# ABS-Pro-Mini.net
KiCad netlist of a schematic drawn in EAGLE
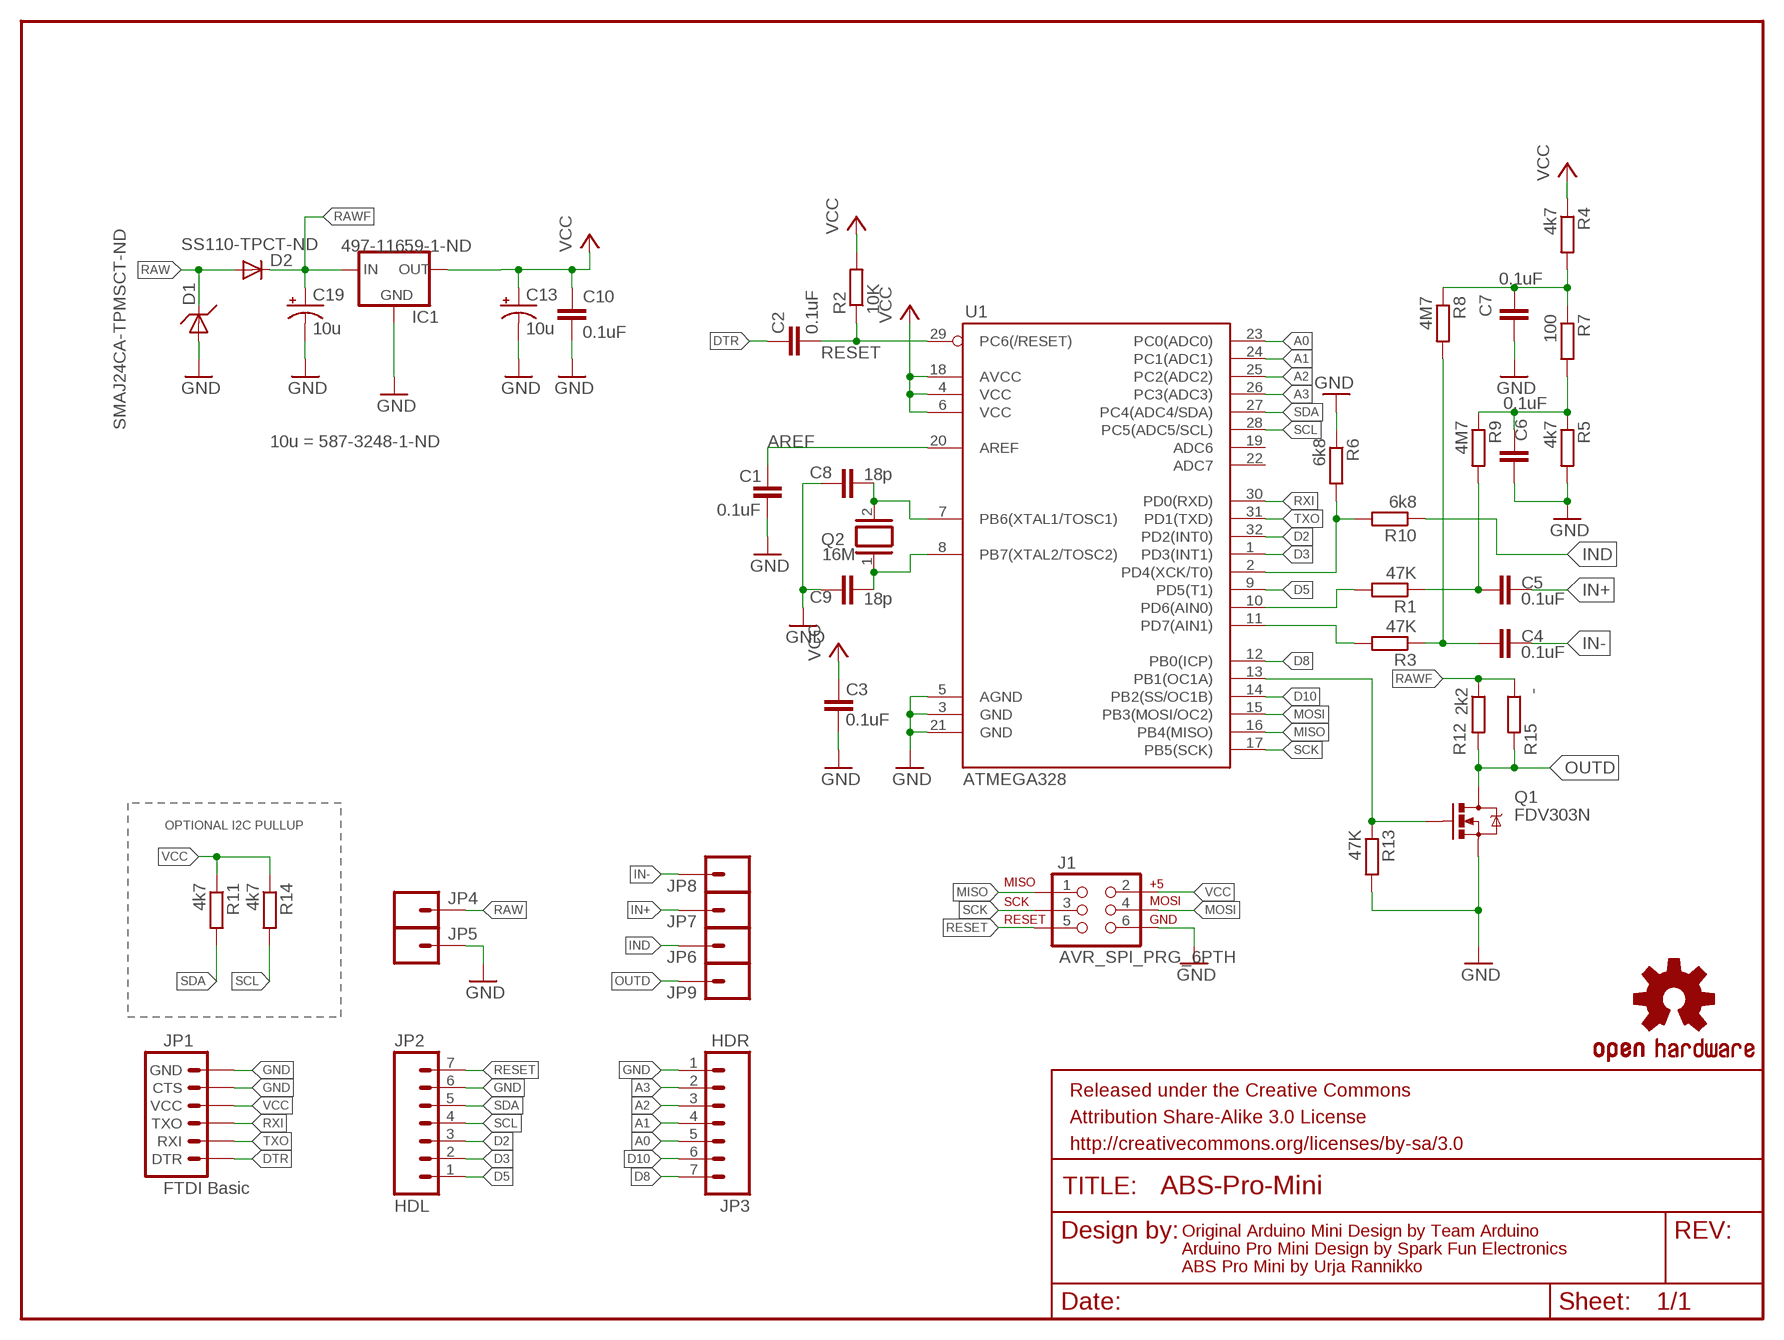
[diagram p0: schematic, sheet 1]

(export (version "E")
  (design (tool "Eeschema 10.0.6"))
  (components
    (comp (ref "C1")
      (value "0.1uF")
      (footprint "eagle-import:0603-CAP")
      (libsource (lib "eagle-import") (part "CAP0603-CAP"))
    )
    (comp (ref "C2")
      (value "0.1uF")
      (footprint "eagle-import:0603-CAP")
      (libsource (lib "eagle-import") (part "CAP0603-CAP"))
    )
    (comp (ref "C3")
      (value "0.1uF")
      (footprint "eagle-import:0603-CAP")
      (libsource (lib "eagle-import") (part "CAP0603-CAP"))
    )
    (comp (ref "C4")
      (value "0.1uF")
      (footprint "eagle-import:0603-CAP")
      (libsource (lib "eagle-import") (part "CAP0603-CAP"))
    )
    (comp (ref "C5")
      (value "0.1uF")
      (footprint "eagle-import:0603-CAP")
      (libsource (lib "eagle-import") (part "CAP0603-CAP"))
    )
    (comp (ref "C6")
      (value "0.1uF")
      (footprint "eagle-import:0603-CAP")
      (libsource (lib "eagle-import") (part "CAP0603-CAP"))
    )
    (comp (ref "C7")
      (value "0.1uF")
      (footprint "eagle-import:0603-CAP")
      (libsource (lib "eagle-import") (part "CAP0603-CAP"))
    )
    (comp (ref "C8")
      (value "18p")
      (footprint "eagle-import:0603-CAP")
      (libsource (lib "eagle-import") (part "CAP0603-CAP"))
    )
    (comp (ref "C9")
      (value "18p")
      (footprint "eagle-import:0603-CAP")
      (libsource (lib "eagle-import") (part "CAP0603-CAP"))
    )
    (comp (ref "C10")
      (value "0.1uF")
      (footprint "eagle-import:0603-CAP")
      (libsource (lib "eagle-import") (part "CAP0603-CAP"))
    )
    (comp (ref "C13")
      (value "10u")
      (footprint "eagle-import:EIA3216")
      (libsource (lib "eagle-import") (part "CAP_POL1206"))
    )
    (comp (ref "C19")
      (value "10u")
      (footprint "eagle-import:EIA3216")
      (libsource (lib "eagle-import") (part "CAP_POL1206"))
    )
    (comp (ref "D1")
      (value "SMAJ24CA-TPMSCT-ND")
      (footprint "eagle-import:SMA-DIODE")
      (libsource (lib "eagle-import") (part "DIODESMA"))
    )
    (comp (ref "D2")
      (value "SS110-TPCT-ND")
      (footprint "eagle-import:SMA-DIODE")
      (libsource (lib "eagle-import") (part "DIODESMA"))
    )
    (comp (ref "FRAME1")
      (value "FRAME-LETTER")
      (footprint "eagle-import:CREATIVE_COMMONS")
      (libsource (lib "eagle-import") (part "FRAME-LETTER"))
    )
    (comp (ref "IC1")
      (value "497-11659-1-ND")
      (footprint "eagle-import:SOT223")
      (libsource (lib "eagle-import") (part "V_REG_MIC2920MG"))
    )
    (comp (ref "J1")
      (value "AVR_SPI_PRG_6PTH")
      (footprint "eagle-import:2X3")
      (libsource (lib "eagle-import") (part "AVR_SPI_PRG_6PTH"))
    )
    (comp (ref "JP1")
      (value "FTDI Basic")
      (footprint "eagle-import:1X06")
      (libsource (lib "eagle-import") (part "ARDUINO_SERIAL_PROGRAMPTH"))
    )
    (comp (ref "JP2")
      (value "HDL")
      (footprint "eagle-import:1X07")
      (libsource (lib "eagle-import") (part "M07"))
    )
    (comp (ref "JP3")
      (value "HDR")
      (footprint "eagle-import:1X07")
      (libsource (lib "eagle-import") (part "M07"))
    )
    (comp (ref "JP4")
      (value "M01PTH_2MM")
      (footprint "eagle-import:1X01_2MM")
      (libsource (lib "eagle-import") (part "M01PTH_2MM"))
    )
    (comp (ref "JP5")
      (value "M01PTH_2MM")
      (footprint "eagle-import:1X01_2MM")
      (libsource (lib "eagle-import") (part "M01PTH_2MM"))
    )
    (comp (ref "JP6")
      (value "M01PTH_2MM")
      (footprint "eagle-import:1X01_2MM")
      (libsource (lib "eagle-import") (part "M01PTH_2MM"))
    )
    (comp (ref "JP7")
      (value "M01PTH_2MM")
      (footprint "eagle-import:1X01_2MM")
      (libsource (lib "eagle-import") (part "M01PTH_2MM"))
    )
    (comp (ref "JP8")
      (value "M01PTH_2MM")
      (footprint "eagle-import:1X01_2MM")
      (libsource (lib "eagle-import") (part "M01PTH_2MM"))
    )
    (comp (ref "JP9")
      (value "M01PTH_2MM")
      (footprint "eagle-import:1X01_2MM")
      (libsource (lib "eagle-import") (part "M01PTH_2MM"))
    )
    (comp (ref "Q1")
      (value "FDV303N")
      (footprint "eagle-import:SOT23")
      (libsource (lib "eagle-import") (part "MOSFET-NCHANNELBSS123LT1G"))
    )
    (comp (ref "Q2")
      (value "16M")
      (footprint "eagle-import:QS")
      (libsource (lib "eagle-import") (part "XTAL/S"))
    )
    (comp (ref "R1")
      (value "47K")
      (footprint "eagle-import:R0805")
      (libsource (lib "eagle-import") (part "R-EU_R0805"))
    )
    (comp (ref "R2")
      (value "10K")
      (footprint "eagle-import:R0805")
      (libsource (lib "eagle-import") (part "R-EU_R0805"))
    )
    (comp (ref "R3")
      (value "47K")
      (footprint "eagle-import:R0805")
      (libsource (lib "eagle-import") (part "R-EU_R0805"))
    )
    (comp (ref "R4")
      (value "4k7")
      (footprint "eagle-import:R0805")
      (libsource (lib "eagle-import") (part "R-EU_R0805"))
    )
    (comp (ref "R5")
      (value "4k7")
      (footprint "eagle-import:R0805")
      (libsource (lib "eagle-import") (part "R-EU_R0805"))
    )
    (comp (ref "R6")
      (value "6k8")
      (footprint "eagle-import:R0805")
      (libsource (lib "eagle-import") (part "R-EU_R0805"))
    )
    (comp (ref "R7")
      (value "100")
      (footprint "eagle-import:R0805")
      (libsource (lib "eagle-import") (part "R-EU_R0805"))
    )
    (comp (ref "R8")
      (value "4M7")
      (footprint "eagle-import:0207_12")
      (libsource (lib "eagle-import") (part "R-EU_0207/12"))
    )
    (comp (ref "R9")
      (value "4M7")
      (footprint "eagle-import:0207_12")
      (libsource (lib "eagle-import") (part "R-EU_0207/12"))
    )
    (comp (ref "R10")
      (value "6k8")
      (footprint "eagle-import:R0805")
      (libsource (lib "eagle-import") (part "R-EU_R0805"))
    )
    (comp (ref "R11")
      (value "4k7")
      (footprint "eagle-import:R0805")
      (libsource (lib "eagle-import") (part "R-EU_R0805"))
    )
    (comp (ref "R12")
      (value "2k2")
      (footprint "eagle-import:R0805")
      (libsource (lib "eagle-import") (part "R-EU_R0805"))
    )
    (comp (ref "R13")
      (value "47K")
      (footprint "eagle-import:R0805")
      (libsource (lib "eagle-import") (part "R-EU_R0805"))
    )
    (comp (ref "R14")
      (value "4k7")
      (footprint "eagle-import:R0805")
      (libsource (lib "eagle-import") (part "R-EU_R0805"))
    )
    (comp (ref "R15")
      (value "-")
      (footprint "eagle-import:R0805")
      (libsource (lib "eagle-import") (part "R-EU_R0805"))
    )
    (comp (ref "U$3")
      (value "OSHW-LOGOS")
      (footprint "eagle-import:OSHW-LOGO-S")
      (libsource (lib "eagle-import") (part "OSHW-LOGOS"))
    )
    (comp (ref "U1")
      (value "ATMEGA328")
      (footprint "eagle-import:TQFP32-08")
      (libsource (lib "eagle-import") (part "ATMEGA168"))
    )
  )
  (nets
    (net (code "1") (name "/AREF") (class "Default")
      (node (ref "C1") (pin "2") (pinfunction "2_2") (pintype "passive"))
      (node (ref "U1") (pin "20") (pinfunction "AREF_20") (pintype "bidirectional"))
    )
    (net (code "2") (name "A0") (class "Default")
      (node (ref "JP3") (pin "5") (pinfunction "5_5") (pintype "passive"))
      (node (ref "U1") (pin "23") (pinfunction "PC0(ADC0)_23") (pintype "bidirectional"))
    )
    (net (code "3") (name "A1") (class "Default")
      (node (ref "JP3") (pin "4") (pinfunction "4_4") (pintype "passive"))
      (node (ref "U1") (pin "24") (pinfunction "PC1(ADC1)_24") (pintype "bidirectional"))
    )
    (net (code "4") (name "A2") (class "Default")
      (node (ref "JP3") (pin "3") (pinfunction "3_3") (pintype "passive"))
      (node (ref "U1") (pin "25") (pinfunction "PC2(ADC2)_25") (pintype "bidirectional"))
    )
    (net (code "5") (name "A3") (class "Default")
      (node (ref "JP3") (pin "2") (pinfunction "2_2") (pintype "passive"))
      (node (ref "U1") (pin "26") (pinfunction "PC3(ADC3)_26") (pintype "bidirectional"))
    )
    (net (code "6") (name "D2") (class "Default")
      (node (ref "JP2") (pin "3") (pinfunction "3_3") (pintype "passive"))
      (node (ref "U1") (pin "32") (pinfunction "PD2(INT0)_32") (pintype "bidirectional"))
    )
    (net (code "7") (name "D3") (class "Default")
      (node (ref "JP2") (pin "2") (pinfunction "2_2") (pintype "passive"))
      (node (ref "U1") (pin "1") (pinfunction "PD3(INT1)_1") (pintype "bidirectional"))
    )
    (net (code "8") (name "D5") (class "Default")
      (node (ref "JP2") (pin "1") (pinfunction "1_1") (pintype "passive"))
      (node (ref "U1") (pin "9") (pinfunction "PD5(T1)_9") (pintype "bidirectional"))
    )
    (net (code "9") (name "D8") (class "Default")
      (node (ref "JP3") (pin "7") (pinfunction "7_7") (pintype "passive"))
      (node (ref "U1") (pin "12") (pinfunction "PB0(ICP)_12") (pintype "bidirectional"))
    )
    (net (code "10") (name "D10") (class "Default")
      (node (ref "JP3") (pin "6") (pinfunction "6_6") (pintype "passive"))
      (node (ref "U1") (pin "14") (pinfunction "PB2(SS/OC1B)_14") (pintype "bidirectional"))
    )
    (net (code "11") (name "DTR") (class "Default")
      (node (ref "C2") (pin "2") (pinfunction "2_2") (pintype "passive"))
      (node (ref "JP1") (pin "1") (pinfunction "DTR_1") (pintype "passive"))
    )
    (net (code "12") (name "GND") (class "Default")
      (node (ref "C1") (pin "1") (pinfunction "1_1") (pintype "passive"))
      (node (ref "C10") (pin "2") (pinfunction "2_2") (pintype "passive"))
      (node (ref "C13") (pin "C") (pinfunction "-_C") (pintype "passive"))
      (node (ref "C19") (pin "C") (pinfunction "-_C") (pintype "passive"))
      (node (ref "C3") (pin "1") (pinfunction "1_1") (pintype "passive"))
      (node (ref "C6") (pin "2") (pinfunction "2_2") (pintype "passive"))
      (node (ref "C7") (pin "2") (pinfunction "2_2") (pintype "passive"))
      (node (ref "C8") (pin "2") (pinfunction "2_2") (pintype "passive"))
      (node (ref "C9") (pin "2") (pinfunction "2_2") (pintype "passive"))
      (node (ref "D1") (pin "A") (pinfunction "A_A") (pintype "passive"))
      (node (ref "IC1") (pin "2") (pinfunction "GND_2") (pintype "input"))
      (node (ref "IC1") (pin "4") (pinfunction "GND_4") (pintype "input"))
      (node (ref "J1") (pin "6") (pinfunction "6_6") (pintype "passive"))
      (node (ref "JP1") (pin "5") (pinfunction "CTS_5") (pintype "passive"))
      (node (ref "JP1") (pin "6") (pinfunction "GND_6") (pintype "passive"))
      (node (ref "JP2") (pin "6") (pinfunction "6_6") (pintype "passive"))
      (node (ref "JP3") (pin "1") (pinfunction "1_1") (pintype "passive"))
      (node (ref "JP5") (pin "1") (pinfunction "1_1") (pintype "passive"))
      (node (ref "Q1") (pin "2") (pinfunction "S_2") (pintype "passive"))
      (node (ref "R13") (pin "2") (pinfunction "2_2") (pintype "passive"))
      (node (ref "R5") (pin "2") (pinfunction "2_2") (pintype "passive"))
      (node (ref "R6") (pin "1") (pinfunction "1_1") (pintype "passive"))
      (node (ref "U1") (pin "21") (pinfunction "GND_21") (pintype "bidirectional"))
      (node (ref "U1") (pin "3") (pinfunction "GND_3") (pintype "bidirectional"))
      (node (ref "U1") (pin "5") (pinfunction "AGND_5") (pintype "bidirectional"))
    )
    (net (code "13") (name "IN+") (class "Default")
      (node (ref "C5") (pin "1") (pinfunction "1_1") (pintype "passive"))
      (node (ref "JP7") (pin "1") (pinfunction "1_1") (pintype "passive"))
    )
    (net (code "14") (name "IN-") (class "Default")
      (node (ref "C4") (pin "1") (pinfunction "1_1") (pintype "passive"))
      (node (ref "JP8") (pin "1") (pinfunction "1_1") (pintype "passive"))
    )
    (net (code "15") (name "IND") (class "Default")
      (node (ref "JP6") (pin "1") (pinfunction "1_1") (pintype "passive"))
      (node (ref "R10") (pin "1") (pinfunction "1_1") (pintype "passive"))
    )
    (net (code "16") (name "MISO") (class "Default")
      (node (ref "J1") (pin "1") (pinfunction "1_1") (pintype "passive"))
      (node (ref "U1") (pin "16") (pinfunction "PB4(MISO)_16") (pintype "bidirectional"))
    )
    (net (code "17") (name "MOSI") (class "Default")
      (node (ref "J1") (pin "4") (pinfunction "4_4") (pintype "passive"))
      (node (ref "U1") (pin "15") (pinfunction "PB3(MOSI/OC2)_15") (pintype "bidirectional"))
    )
    (net (code "18") (name "Net-(C4-Pad2)") (class "Default")
      (node (ref "C4") (pin "2") (pinfunction "2_2") (pintype "passive"))
      (node (ref "R3") (pin "1") (pinfunction "1_1") (pintype "passive"))
      (node (ref "R8") (pin "2") (pinfunction "2_2") (pintype "passive"))
    )
    (net (code "19") (name "Net-(C5-Pad2)") (class "Default")
      (node (ref "C5") (pin "2") (pinfunction "2_2") (pintype "passive"))
      (node (ref "R1") (pin "1") (pinfunction "1_1") (pintype "passive"))
      (node (ref "R9") (pin "2") (pinfunction "2_2") (pintype "passive"))
    )
    (net (code "20") (name "Net-(C6-Pad1)") (class "Default")
      (node (ref "C6") (pin "1") (pinfunction "1_1") (pintype "passive"))
      (node (ref "R5") (pin "1") (pinfunction "1_1") (pintype "passive"))
      (node (ref "R7") (pin "2") (pinfunction "2_2") (pintype "passive"))
      (node (ref "R9") (pin "1") (pinfunction "1_1") (pintype "passive"))
    )
    (net (code "21") (name "Net-(C7-Pad1)") (class "Default")
      (node (ref "C7") (pin "1") (pinfunction "1_1") (pintype "passive"))
      (node (ref "R4") (pin "2") (pinfunction "2_2") (pintype "passive"))
      (node (ref "R7") (pin "1") (pinfunction "1_1") (pintype "passive"))
      (node (ref "R8") (pin "1") (pinfunction "1_1") (pintype "passive"))
    )
    (net (code "22") (name "Net-(Q1-G)") (class "Default")
      (node (ref "Q1") (pin "1") (pinfunction "G_1") (pintype "passive"))
      (node (ref "R13") (pin "1") (pinfunction "1_1") (pintype "passive"))
      (node (ref "U1") (pin "13") (pinfunction "PB1(OC1A)_13") (pintype "bidirectional"))
    )
    (net (code "23") (name "Net-(U1-PB6(XTAL1{slash}TOSC1))") (class "Default")
      (node (ref "C8") (pin "1") (pinfunction "1_1") (pintype "passive"))
      (node (ref "Q2") (pin "2") (pinfunction "2_2") (pintype "passive"))
      (node (ref "U1") (pin "7") (pinfunction "PB6(XTAL1/TOSC1)_7") (pintype "bidirectional"))
    )
    (net (code "24") (name "Net-(U1-PB7(XTAL2{slash}TOSC2))") (class "Default")
      (node (ref "C9") (pin "1") (pinfunction "1_1") (pintype "passive"))
      (node (ref "Q2") (pin "1") (pinfunction "1_1") (pintype "passive"))
      (node (ref "U1") (pin "8") (pinfunction "PB7(XTAL2/TOSC2)_8") (pintype "bidirectional"))
    )
    (net (code "25") (name "Net-(U1-PD4(XCK{slash}T0))") (class "Default")
      (node (ref "R10") (pin "2") (pinfunction "2_2") (pintype "passive"))
      (node (ref "R6") (pin "2") (pinfunction "2_2") (pintype "passive"))
      (node (ref "U1") (pin "2") (pinfunction "PD4(XCK/T0)_2") (pintype "bidirectional"))
    )
    (net (code "26") (name "Net-(U1-PD6(AIN0))") (class "Default")
      (node (ref "R1") (pin "2") (pinfunction "2_2") (pintype "passive"))
      (node (ref "U1") (pin "10") (pinfunction "PD6(AIN0)_10") (pintype "bidirectional"))
    )
    (net (code "27") (name "Net-(U1-PD7(AIN1))") (class "Default")
      (node (ref "R3") (pin "2") (pinfunction "2_2") (pintype "passive"))
      (node (ref "U1") (pin "11") (pinfunction "PD7(AIN1)_11") (pintype "bidirectional"))
    )
    (net (code "28") (name "OUTD") (class "Default")
      (node (ref "JP9") (pin "1") (pinfunction "1_1") (pintype "passive"))
      (node (ref "Q1") (pin "3") (pinfunction "D_3") (pintype "passive"))
      (node (ref "R12") (pin "2") (pinfunction "2_2") (pintype "passive"))
      (node (ref "R15") (pin "2") (pinfunction "2_2") (pintype "passive"))
    )
    (net (code "29") (name "RAW") (class "Default")
      (node (ref "D1") (pin "C") (pinfunction "C_C") (pintype "passive"))
      (node (ref "D2") (pin "A") (pinfunction "A_A") (pintype "passive"))
      (node (ref "JP4") (pin "1") (pinfunction "1_1") (pintype "passive"))
    )
    (net (code "30") (name "RAWF") (class "Default")
      (node (ref "C19") (pin "A") (pinfunction "+_A") (pintype "passive"))
      (node (ref "D2") (pin "C") (pinfunction "C_C") (pintype "passive"))
      (node (ref "IC1") (pin "1") (pinfunction "IN_1") (pintype "input"))
      (node (ref "R12") (pin "1") (pinfunction "1_1") (pintype "passive"))
      (node (ref "R15") (pin "1") (pinfunction "1_1") (pintype "passive"))
    )
    (net (code "31") (name "RESET") (class "Default")
      (node (ref "C2") (pin "1") (pinfunction "1_1") (pintype "passive"))
      (node (ref "J1") (pin "5") (pinfunction "5_5") (pintype "passive"))
      (node (ref "JP2") (pin "7") (pinfunction "7_7") (pintype "passive"))
      (node (ref "R2") (pin "1") (pinfunction "1_1") (pintype "passive"))
      (node (ref "U1") (pin "29") (pinfunction "PC6(/RESET)_29") (pintype "bidirectional"))
    )
    (net (code "32") (name "RXI") (class "Default")
      (node (ref "JP1") (pin "3") (pinfunction "TXO_3") (pintype "passive"))
      (node (ref "U1") (pin "30") (pinfunction "PD0(RXD)_30") (pintype "bidirectional"))
    )
    (net (code "33") (name "SCK") (class "Default")
      (node (ref "J1") (pin "3") (pinfunction "3_3") (pintype "passive"))
      (node (ref "U1") (pin "17") (pinfunction "PB5(SCK)_17") (pintype "bidirectional"))
    )
    (net (code "34") (name "SCL") (class "Default")
      (node (ref "JP2") (pin "4") (pinfunction "4_4") (pintype "passive"))
      (node (ref "R14") (pin "2") (pinfunction "2_2") (pintype "passive"))
      (node (ref "U1") (pin "28") (pinfunction "PC5(ADC5/SCL)_28") (pintype "bidirectional"))
    )
    (net (code "35") (name "SDA") (class "Default")
      (node (ref "JP2") (pin "5") (pinfunction "5_5") (pintype "passive"))
      (node (ref "R11") (pin "2") (pinfunction "2_2") (pintype "passive"))
      (node (ref "U1") (pin "27") (pinfunction "PC4(ADC4/SDA)_27") (pintype "bidirectional"))
    )
    (net (code "36") (name "TXO") (class "Default")
      (node (ref "JP1") (pin "2") (pinfunction "RXI_2") (pintype "passive"))
      (node (ref "U1") (pin "31") (pinfunction "PD1(TXD)_31") (pintype "bidirectional"))
    )
    (net (code "37") (name "VCC") (class "Default")
      (node (ref "C10") (pin "1") (pinfunction "1_1") (pintype "passive"))
      (node (ref "C13") (pin "A") (pinfunction "+_A") (pintype "passive"))
      (node (ref "C3") (pin "2") (pinfunction "2_2") (pintype "passive"))
      (node (ref "IC1") (pin "3") (pinfunction "OUT_3") (pintype "output"))
      (node (ref "J1") (pin "2") (pinfunction "2_2") (pintype "passive"))
      (node (ref "JP1") (pin "4") (pinfunction "VCC_4") (pintype "passive"))
      (node (ref "R11") (pin "1") (pinfunction "1_1") (pintype "passive"))
      (node (ref "R14") (pin "1") (pinfunction "1_1") (pintype "passive"))
      (node (ref "R2") (pin "2") (pinfunction "2_2") (pintype "passive"))
      (node (ref "R4") (pin "1") (pinfunction "1_1") (pintype "passive"))
      (node (ref "U1") (pin "18") (pinfunction "AVCC_18") (pintype "bidirectional"))
      (node (ref "U1") (pin "4") (pinfunction "VCC_4") (pintype "bidirectional"))
      (node (ref "U1") (pin "6") (pinfunction "VCC_6") (pintype "bidirectional"))
    )
    (net (code "38") (name "unconnected-(U1-ADC6-Pad19)") (class "Default")
      (node (ref "U1") (pin "19") (pinfunction "ADC6_19") (pintype "bidirectional"))
    )
    (net (code "39") (name "unconnected-(U1-ADC7-Pad22)") (class "Default")
      (node (ref "U1") (pin "22") (pinfunction "ADC7_22") (pintype "bidirectional"))
    )
  )
)
